# Sensor_Suite_1.net
KiCad netlist of a schematic drawn in Altium Designer
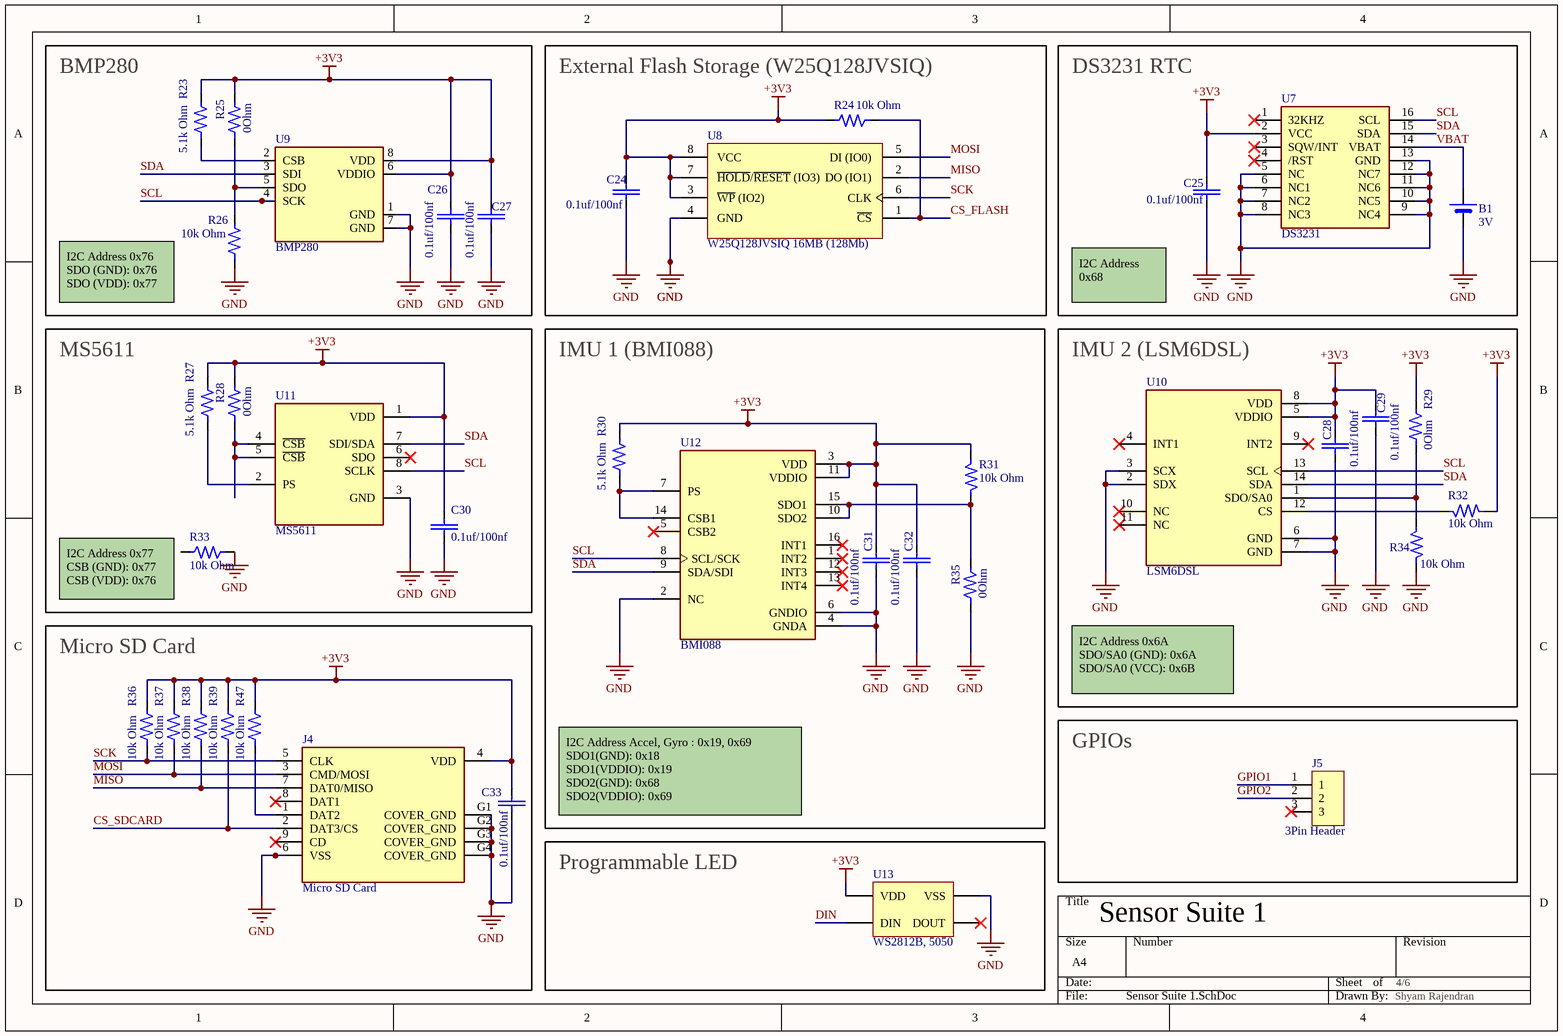
[diagram p0: Sensor Suite 1.SchDoc]

(export (version "E")
  (design (tool "Eeschema 10.0.6"))
  (components
    (comp (ref "B1")
      (value "3V")
      (footprint "Battery Holder")
      (description "CR2032 Button Cell")
      (libsource (lib "Sirius") (part "Button Cell"))
    )
    (comp (ref "C24")
      (value "0.1uf/100nf")
      (footprint "0.1uF Capacitor")
      (description "0.1 uF, Multilayer Ceramic Capacitor, 50 V, ï¿½ 10%, X7R, 0805 [2012 Metric]")
      (fields
        (field (name "MANUFACTURER") "Yageo")
        (field (name "MANUFACTURER PART NUMBER") "CC0805KRX7R9BB104")
      )
      (libsource (lib "Sirius") (part "CC0805KRX7R9BB104"))
    )
    (comp (ref "C25")
      (value "0.1uf/100nf")
      (footprint "0.1uF Capacitor")
      (description "0.1 uF, Multilayer Ceramic Capacitor, 50 V, ï¿½ 10%, X7R, 0805 [2012 Metric]")
      (fields
        (field (name "MANUFACTURER") "Yageo")
        (field (name "MANUFACTURER PART NUMBER") "CC0805KRX7R9BB104")
      )
      (libsource (lib "Sirius") (part "CC0805KRX7R9BB104"))
    )
    (comp (ref "C26")
      (value "0.1uf/100nf")
      (footprint "0.1uF Capacitor")
      (description "0.1 uF, Multilayer Ceramic Capacitor, 50 V, ï¿½ 10%, X7R, 0805 [2012 Metric]")
      (fields
        (field (name "MANUFACTURER") "Yageo")
        (field (name "MANUFACTURER PART NUMBER") "CC0805KRX7R9BB104")
      )
      (libsource (lib "Sirius") (part "CC0805KRX7R9BB104"))
    )
    (comp (ref "C27")
      (value "0.1uf/100nf")
      (footprint "0.1uF Capacitor")
      (description "0.1 uF, Multilayer Ceramic Capacitor, 50 V, ï¿½ 10%, X7R, 0805 [2012 Metric]")
      (fields
        (field (name "MANUFACTURER") "Yageo")
        (field (name "MANUFACTURER PART NUMBER") "CC0805KRX7R9BB104")
      )
      (libsource (lib "Sirius") (part "CC0805KRX7R9BB104"))
    )
    (comp (ref "C28")
      (value "0.1uf/100nf")
      (footprint "0.1uF Capacitor")
      (description "0.1 uF, Multilayer Ceramic Capacitor, 50 V, ï¿½ 10%, X7R, 0805 [2012 Metric]")
      (fields
        (field (name "MANUFACTURER") "Yageo")
        (field (name "MANUFACTURER PART NUMBER") "CC0805KRX7R9BB104")
      )
      (libsource (lib "Sirius") (part "CC0805KRX7R9BB104"))
    )
    (comp (ref "C29")
      (value "0.1uf/100nf")
      (footprint "0.1uF Capacitor")
      (description "0.1 uF, Multilayer Ceramic Capacitor, 50 V, ï¿½ 10%, X7R, 0805 [2012 Metric]")
      (fields
        (field (name "MANUFACTURER") "Yageo")
        (field (name "MANUFACTURER PART NUMBER") "CC0805KRX7R9BB104")
      )
      (libsource (lib "Sirius") (part "CC0805KRX7R9BB104"))
    )
    (comp (ref "C30")
      (value "0.1uf/100nf")
      (footprint "0.1uF Capacitor")
      (description "0.1 uF, Multilayer Ceramic Capacitor, 50 V, ï¿½ 10%, X7R, 0805 [2012 Metric]")
      (fields
        (field (name "MANUFACTURER") "Yageo")
        (field (name "MANUFACTURER PART NUMBER") "CC0805KRX7R9BB104")
      )
      (libsource (lib "Sirius") (part "CC0805KRX7R9BB104"))
    )
    (comp (ref "C31")
      (value "0.1uf/100nf")
      (footprint "0.1uF Capacitor")
      (description "0.1 uF, Multilayer Ceramic Capacitor, 50 V, ï¿½ 10%, X7R, 0805 [2012 Metric]")
      (fields
        (field (name "MANUFACTURER") "Yageo")
        (field (name "MANUFACTURER PART NUMBER") "CC0805KRX7R9BB104")
      )
      (libsource (lib "Sirius") (part "CC0805KRX7R9BB104"))
    )
    (comp (ref "C32")
      (value "0.1uf/100nf")
      (footprint "0.1uF Capacitor")
      (description "0.1 uF, Multilayer Ceramic Capacitor, 50 V, ï¿½ 10%, X7R, 0805 [2012 Metric]")
      (fields
        (field (name "MANUFACTURER") "Yageo")
        (field (name "MANUFACTURER PART NUMBER") "CC0805KRX7R9BB104")
      )
      (libsource (lib "Sirius") (part "CC0805KRX7R9BB104"))
    )
    (comp (ref "C33")
      (value "0.1uf/100nf")
      (footprint "0.1uF Capacitor")
      (description "0.1 uF, Multilayer Ceramic Capacitor, 50 V, ï¿½ 10%, X7R, 0805 [2012 Metric]")
      (fields
        (field (name "MANUFACTURER") "Yageo")
        (field (name "MANUFACTURER PART NUMBER") "CC0805KRX7R9BB104")
      )
      (libsource (lib "Sirius") (part "CC0805KRX7R9BB104"))
    )
    (comp (ref "J4")
      (value "Micro SD Card")
      (footprint "Micro SD Card")
      (fields (field (name "MF") "CUI Devices") (field (name "MP") "MSD-1-A"))
      (libsource (lib "Sirius") (part "Micro SD Card"))
    )
    (comp (ref "J5")
      (value "3Pin Header")
      (footprint "3 Pin Header")
      (libsource (lib "Sirius") (part "Header 3pin"))
    )
    (comp (ref "R23")
      (value "5.1k Ohm")
      (footprint "RESC2012X60N")
      (description "5.1k Ohm, 0805, 0.125W, 150V, 1% +/-Tol, 100ppm/Cel, Surface Mount")
      (fields
        (field (name "MANUFACTURER") "Yageo")
        (field (name "MANUFACTURER PART NUMBER") "RC0805FR-075K1L")
      )
      (libsource (lib "Sirius") (part "RC0805FR-075K1L"))
    )
    (comp (ref "R24")
      (value "10k Ohm")
      (footprint "RESC2013X60X35ML10T20")
      (description "10 kOhm, SMD Chip Resistor, ï¿½ 1%, 125 mW, 0805 [2012 Metric], Thick Film, General Purpose")
      (fields
        (field (name "MANUFACTURER") "Yageo")
        (field (name "MANUFACTURER PART NUMBER") "RC0805FR-0710KL")
      )
      (libsource (lib "Sirius") (part "RC0805FR-0710KL"))
    )
    (comp (ref "R25")
      (value "0Ohm")
      (footprint "1k 0805 Resistor")
      (description "0 Ohm Resistor, Jumper, 0805 [2012 Metric], Thick Film, 125 mW, Surface Mount")
      (fields
        (field (name "MANUFACTURER") "Vishay")
        (field (name "MANUFACTURER PART NUMBER") "CRCW08050000Z0EA")
      )
      (libsource (lib "Sirius") (part "CRCW08050000Z0EA"))
    )
    (comp (ref "R26")
      (value "10k Ohm")
      (footprint "RESC2013X60X35ML10T20")
      (description "10 kOhm, SMD Chip Resistor, ï¿½ 1%, 125 mW, 0805 [2012 Metric], Thick Film, General Purpose")
      (fields
        (field (name "MANUFACTURER") "Yageo")
        (field (name "MANUFACTURER PART NUMBER") "RC0805FR-0710KL")
      )
      (libsource (lib "Sirius") (part "RC0805FR-0710KL"))
    )
    (comp (ref "R27")
      (value "5.1k Ohm")
      (footprint "RESC2012X60N")
      (description "5.1k Ohm, 0805, 0.125W, 150V, 1% +/-Tol, 100ppm/Cel, Surface Mount")
      (fields
        (field (name "MANUFACTURER") "Yageo")
        (field (name "MANUFACTURER PART NUMBER") "RC0805FR-075K1L")
      )
      (libsource (lib "Sirius") (part "RC0805FR-075K1L"))
    )
    (comp (ref "R28")
      (value "0Ohm")
      (footprint "1k 0805 Resistor")
      (description "0 Ohm Resistor, Jumper, 0805 [2012 Metric], Thick Film, 125 mW, Surface Mount")
      (fields
        (field (name "MANUFACTURER") "Vishay")
        (field (name "MANUFACTURER PART NUMBER") "CRCW08050000Z0EA")
      )
      (libsource (lib "Sirius") (part "CRCW08050000Z0EA"))
    )
    (comp (ref "R29")
      (value "0Ohm")
      (footprint "1k 0805 Resistor")
      (description "0 Ohm Resistor, Jumper, 0805 [2012 Metric], Thick Film, 125 mW, Surface Mount")
      (fields
        (field (name "MANUFACTURER") "Vishay")
        (field (name "MANUFACTURER PART NUMBER") "CRCW08050000Z0EA")
      )
      (libsource (lib "Sirius") (part "CRCW08050000Z0EA"))
    )
    (comp (ref "R30")
      (value "5.1k Ohm")
      (footprint "RESC2012X60N")
      (description "5.1k Ohm, 0805, 0.125W, 150V, 1% +/-Tol, 100ppm/Cel, Surface Mount")
      (fields
        (field (name "MANUFACTURER") "Yageo")
        (field (name "MANUFACTURER PART NUMBER") "RC0805FR-075K1L")
      )
      (libsource (lib "Sirius") (part "RC0805FR-075K1L"))
    )
    (comp (ref "R31")
      (value "10k Ohm")
      (footprint "RESC2013X60X35ML10T20")
      (description "10 kOhm, SMD Chip Resistor, ï¿½ 1%, 125 mW, 0805 [2012 Metric], Thick Film, General Purpose")
      (fields
        (field (name "MANUFACTURER") "Yageo")
        (field (name "MANUFACTURER PART NUMBER") "RC0805FR-0710KL")
      )
      (libsource (lib "Sirius") (part "RC0805FR-0710KL"))
    )
    (comp (ref "R32")
      (value "10k Ohm")
      (footprint "RESC2013X60X35ML10T20")
      (description "10 kOhm, SMD Chip Resistor, ï¿½ 1%, 125 mW, 0805 [2012 Metric], Thick Film, General Purpose")
      (fields
        (field (name "MANUFACTURER") "Yageo")
        (field (name "MANUFACTURER PART NUMBER") "RC0805FR-0710KL")
      )
      (libsource (lib "Sirius") (part "RC0805FR-0710KL"))
    )
    (comp (ref "R33")
      (value "10k Ohm")
      (footprint "RESC2013X60X35ML10T20")
      (description "10 kOhm, SMD Chip Resistor, ï¿½ 1%, 125 mW, 0805 [2012 Metric], Thick Film, General Purpose")
      (fields
        (field (name "MANUFACTURER") "Yageo")
        (field (name "MANUFACTURER PART NUMBER") "RC0805FR-0710KL")
      )
      (libsource (lib "Sirius") (part "RC0805FR-0710KL"))
    )
    (comp (ref "R34")
      (value "10k Ohm")
      (footprint "RESC2013X60X35ML10T20")
      (description "10 kOhm, SMD Chip Resistor, ï¿½ 1%, 125 mW, 0805 [2012 Metric], Thick Film, General Purpose")
      (fields
        (field (name "MANUFACTURER") "Yageo")
        (field (name "MANUFACTURER PART NUMBER") "RC0805FR-0710KL")
      )
      (libsource (lib "Sirius") (part "RC0805FR-0710KL"))
    )
    (comp (ref "R35")
      (value "0Ohm")
      (footprint "1k 0805 Resistor")
      (description "0 Ohm Resistor, Jumper, 0805 [2012 Metric], Thick Film, 125 mW, Surface Mount")
      (fields
        (field (name "MANUFACTURER") "Vishay")
        (field (name "MANUFACTURER PART NUMBER") "CRCW08050000Z0EA")
      )
      (libsource (lib "Sirius") (part "CRCW08050000Z0EA"))
    )
    (comp (ref "R36")
      (value "10k Ohm")
      (footprint "RESC2013X60X35ML10T20")
      (description "10 kOhm, SMD Chip Resistor, ï¿½ 1%, 125 mW, 0805 [2012 Metric], Thick Film, General Purpose")
      (fields
        (field (name "MANUFACTURER") "Yageo")
        (field (name "MANUFACTURER PART NUMBER") "RC0805FR-0710KL")
      )
      (libsource (lib "Sirius") (part "RC0805FR-0710KL"))
    )
    (comp (ref "R37")
      (value "10k Ohm")
      (footprint "RESC2013X60X35ML10T20")
      (description "10 kOhm, SMD Chip Resistor, ï¿½ 1%, 125 mW, 0805 [2012 Metric], Thick Film, General Purpose")
      (fields
        (field (name "MANUFACTURER") "Yageo")
        (field (name "MANUFACTURER PART NUMBER") "RC0805FR-0710KL")
      )
      (libsource (lib "Sirius") (part "RC0805FR-0710KL"))
    )
    (comp (ref "R38")
      (value "10k Ohm")
      (footprint "RESC2013X60X35ML10T20")
      (description "10 kOhm, SMD Chip Resistor, ï¿½ 1%, 125 mW, 0805 [2012 Metric], Thick Film, General Purpose")
      (fields
        (field (name "MANUFACTURER") "Yageo")
        (field (name "MANUFACTURER PART NUMBER") "RC0805FR-0710KL")
      )
      (libsource (lib "Sirius") (part "RC0805FR-0710KL"))
    )
    (comp (ref "R39")
      (value "10k Ohm")
      (footprint "RESC2013X60X35ML10T20")
      (description "10 kOhm, SMD Chip Resistor, ï¿½ 1%, 125 mW, 0805 [2012 Metric], Thick Film, General Purpose")
      (fields
        (field (name "MANUFACTURER") "Yageo")
        (field (name "MANUFACTURER PART NUMBER") "RC0805FR-0710KL")
      )
      (libsource (lib "Sirius") (part "RC0805FR-0710KL"))
    )
    (comp (ref "R47")
      (value "10k Ohm")
      (footprint "RESC2013X60X35ML10T20")
      (description "10 kOhm, SMD Chip Resistor, ï¿½ 1%, 125 mW, 0805 [2012 Metric], Thick Film, General Purpose")
      (fields
        (field (name "MANUFACTURER") "Yageo")
        (field (name "MANUFACTURER PART NUMBER") "RC0805FR-0710KL")
      )
      (libsource (lib "Sirius") (part "RC0805FR-0710KL"))
    )
    (comp (ref "U7")
      (value "DS3231 RTC")
      (footprint "DS3231")
      (description "Real Time Clock (RTC) IC Clock/Calendar - IÂ²C, 2-Wire Serial 8-SOIC (0.154, 3.90mm Width)")
      (fields (field (name "MP") "DS3231") (field (name "MF") "Maxim Integrated"))
      (libsource (lib "Sirius") (part "DS3231"))
    )
    (comp (ref "U8")
      (value "W25Q128JVSIQ 16MB (128Mb)")
      (footprint "W25Q128JVSIQ")
      (description "16MB (128Mb) Flash, PDSO8")
      (fields
        (field (name "MANUFACTURER") "Winbond")
        (field (name "MANUFACTURER PART NUMBER") "W25Q128JVSIQ TR")
      )
      (libsource (lib "Sirius") (part "W25Q128JVSIQ TR"))
    )
    (comp (ref "U9")
      (value "BMP280")
      (footprint "BMP280")
      (description "BMP280 Absolute Barometric Pressure Sensor for Battery Powered Devices 2 x 2.5mm")
      (libsource (lib "Sirius") (part "BMP280"))
    )
    (comp (ref "U10")
      (value "LSM6DSL")
      (footprint "LSM6DSO32TR")
      (description "Accelerometer, Gyroscope, Temperature, 6 Axis Sensor IÂ²C, SPI Output")
      (fields (field (name "MF") "STMicroelectronics") (field (name "MP") "LSM6DSO32TR"))
      (libsource (lib "Sirius") (part "LSM6DSL"))
    )
    (comp (ref "U11")
      (value "MS5611")
      (footprint "MS561101BA03-50")
      (description "Sensor;MS5611-BT M-CAPS 3X5X1MM T&R;Pressure;MS561101BA03-50 ¦ TE Connectivity MS561101BA03-50")
      (fields (field (name "MF") "TE Connectivity") (field (name "MP") "MS561101BA03-50"))
      (libsource (lib "Sirius") (part "MS561101BA03-50"))
    )
    (comp (ref "U12") (value "BMI088") (footprint "BMI088") (libsource (lib "Sirius") (part "BMI088")))
    (comp (ref "U13")
      (value "WS2812B, 5050")
      (footprint "WS2812B")
      (fields (field (name "MANUFACTURER") "Adafruit-Industries-LLC"))
      (libsource (lib "Sirius") (part "WS2812B"))
    )
  )
  (nets
    (net (code "1") (name "+3V3") (class "Default")
      (node (ref "C24") (pin "1") (pinfunction "1_1") (pintype "passive"))
      (node (ref "C25") (pin "1") (pinfunction "1_1") (pintype "passive"))
      (node (ref "C26") (pin "2") (pinfunction "2_2") (pintype "passive"))
      (node (ref "C27") (pin "2") (pinfunction "2_2") (pintype "passive"))
      (node (ref "C28") (pin "2") (pinfunction "2_2") (pintype "passive"))
      (node (ref "C29") (pin "2") (pinfunction "2_2") (pintype "passive"))
      (node (ref "C30") (pin "2") (pinfunction "2_2") (pintype "passive"))
      (node (ref "C31") (pin "2") (pinfunction "2_2") (pintype "passive"))
      (node (ref "C32") (pin "2") (pinfunction "2_2") (pintype "passive"))
      (node (ref "C33") (pin "2") (pinfunction "2_2") (pintype "passive"))
      (node (ref "J4") (pin "4") (pinfunction "VDD_4") (pintype "passive"))
      (node (ref "R23") (pin "2") (pinfunction "2_2") (pintype "passive"))
      (node (ref "R24") (pin "2") (pinfunction "2_2") (pintype "passive"))
      (node (ref "R25") (pin "2") (pinfunction "2_2") (pintype "passive"))
      (node (ref "R27") (pin "2") (pinfunction "2_2") (pintype "passive"))
      (node (ref "R28") (pin "2") (pinfunction "2_2") (pintype "passive"))
      (node (ref "R29") (pin "2") (pinfunction "2_2") (pintype "passive"))
      (node (ref "R30") (pin "2") (pinfunction "2_2") (pintype "passive"))
      (node (ref "R31") (pin "2") (pinfunction "2_2") (pintype "passive"))
      (node (ref "R32") (pin "1") (pinfunction "1_1") (pintype "passive"))
      (node (ref "R36") (pin "2") (pinfunction "2_2") (pintype "passive"))
      (node (ref "R37") (pin "2") (pinfunction "2_2") (pintype "passive"))
      (node (ref "R38") (pin "2") (pinfunction "2_2") (pintype "passive"))
      (node (ref "R39") (pin "2") (pinfunction "2_2") (pintype "passive"))
      (node (ref "R47") (pin "2") (pinfunction "2_2") (pintype "passive"))
      (node (ref "U10") (pin "5") (pinfunction "VDDIO_5") (pintype "passive"))
      (node (ref "U10") (pin "8") (pinfunction "VDD_8") (pintype "passive"))
      (node (ref "U11") (pin "1") (pinfunction "VDD_1") (pintype "passive"))
      (node (ref "U12") (pin "11") (pinfunction "VDDIO_11") (pintype "passive"))
      (node (ref "U12") (pin "3") (pinfunction "VDD_3") (pintype "passive"))
      (node (ref "U13") (pin "VDD") (pinfunction "VDD_VDD") (pintype "passive"))
      (node (ref "U7") (pin "2") (pinfunction "VCC_2") (pintype "passive"))
      (node (ref "U8") (pin "3") (pinfunction "~{WP}_(IO2)_3") (pintype "passive"))
      (node (ref "U8") (pin "7") (pinfunction "~{HOLD}/~{RESET}_(IO3)_7") (pintype "passive"))
      (node (ref "U8") (pin "8") (pinfunction "VCC_8") (pintype "passive"))
      (node (ref "U9") (pin "6") (pinfunction "VDDIO_6") (pintype "passive"))
      (node (ref "U9") (pin "8") (pinfunction "VDD_8") (pintype "passive"))
    )
    (net (code "2") (name "/CS_FLASH") (class "Default")
      (node (ref "R24") (pin "1") (pinfunction "1_1") (pintype "passive"))
      (node (ref "U8") (pin "1") (pinfunction "~{CS}_1") (pintype "passive"))
    )
    (net (code "3") (name "/CS_SDCARD") (class "Default")
      (node (ref "J4") (pin "2") (pinfunction "DAT3/CS_2") (pintype "passive"))
      (node (ref "R39") (pin "1") (pinfunction "1_1") (pintype "passive"))
    )
    (net (code "4") (name "/DIN") (class "Default")
      (node (ref "U13") (pin "DIN") (pinfunction "DIN_DIN") (pintype "passive"))
    )
    (net (code "5") (name "/GPIO1") (class "Default")
      (node (ref "J5") (pin "1") (pinfunction "1_1") (pintype "passive"))
    )
    (net (code "6") (name "/GPIO2") (class "Default")
      (node (ref "J5") (pin "2") (pinfunction "2_2") (pintype "passive"))
    )
    (net (code "7") (name "/MISO") (class "Default")
      (node (ref "J4") (pin "7") (pinfunction "DAT0/MISO_7") (pintype "passive"))
      (node (ref "R38") (pin "1") (pinfunction "1_1") (pintype "passive"))
      (node (ref "U8") (pin "2") (pinfunction "DO_(IO1)_2") (pintype "passive"))
    )
    (net (code "8") (name "/MOSI") (class "Default")
      (node (ref "J4") (pin "3") (pinfunction "CMD/MOSI_3") (pintype "passive"))
      (node (ref "R37") (pin "1") (pinfunction "1_1") (pintype "passive"))
      (node (ref "U8") (pin "5") (pinfunction "DI_(IO0)_5") (pintype "passive"))
    )
    (net (code "9") (name "/SCK") (class "Default")
      (node (ref "J4") (pin "5") (pinfunction "CLK_5") (pintype "passive"))
      (node (ref "R36") (pin "1") (pinfunction "1_1") (pintype "passive"))
      (node (ref "U8") (pin "6") (pinfunction "CLK_6") (pintype "passive"))
    )
    (net (code "10") (name "/SCL") (class "Default")
      (node (ref "U10") (pin "13") (pinfunction "SCL_13") (pintype "passive"))
      (node (ref "U11") (pin "8") (pinfunction "SCLK_8") (pintype "passive"))
      (node (ref "U12") (pin "8") (pinfunction "SCL/SCK_8") (pintype "passive"))
      (node (ref "U7") (pin "16") (pinfunction "SCL_16") (pintype "passive"))
      (node (ref "U9") (pin "4") (pinfunction "SCK_4") (pintype "passive"))
    )
    (net (code "11") (name "/SDA") (class "Default")
      (node (ref "U10") (pin "14") (pinfunction "SDA_14") (pintype "passive"))
      (node (ref "U11") (pin "7") (pinfunction "SDI/SDA_7") (pintype "passive"))
      (node (ref "U12") (pin "9") (pinfunction "SDA/SDI_9") (pintype "passive"))
      (node (ref "U7") (pin "15") (pinfunction "SDA_15") (pintype "passive"))
      (node (ref "U9") (pin "3") (pinfunction "SDI_3") (pintype "passive"))
    )
    (net (code "12") (name "/VBAT") (class "Default")
      (node (ref "B1") (pin "P") (pinfunction "P_P") (pintype "passive"))
      (node (ref "U7") (pin "14") (pinfunction "VBAT_14") (pintype "passive"))
    )
    (net (code "13") (name "GND") (class "Default")
      (node (ref "B1") (pin "N") (pinfunction "N_N") (pintype "passive"))
      (node (ref "C24") (pin "2") (pinfunction "2_2") (pintype "passive"))
      (node (ref "C25") (pin "2") (pinfunction "2_2") (pintype "passive"))
      (node (ref "C26") (pin "1") (pinfunction "1_1") (pintype "passive"))
      (node (ref "C27") (pin "1") (pinfunction "1_1") (pintype "passive"))
      (node (ref "C28") (pin "1") (pinfunction "1_1") (pintype "passive"))
      (node (ref "C29") (pin "1") (pinfunction "1_1") (pintype "passive"))
      (node (ref "C30") (pin "1") (pinfunction "1_1") (pintype "passive"))
      (node (ref "C31") (pin "1") (pinfunction "1_1") (pintype "passive"))
      (node (ref "C32") (pin "1") (pinfunction "1_1") (pintype "passive"))
      (node (ref "C33") (pin "1") (pinfunction "1_1") (pintype "passive"))
      (node (ref "J4") (pin "6") (pinfunction "VSS_6") (pintype "passive"))
      (node (ref "J4") (pin "G1") (pinfunction "COVER_GND_G1") (pintype "passive"))
      (node (ref "J4") (pin "G2") (pinfunction "COVER_GND_G2") (pintype "passive"))
      (node (ref "J4") (pin "G3") (pinfunction "COVER_GND_G3") (pintype "passive"))
      (node (ref "J4") (pin "G4") (pinfunction "COVER_GND_G4") (pintype "passive"))
      (node (ref "R26") (pin "1") (pinfunction "1_1") (pintype "passive"))
      (node (ref "R33") (pin "1") (pinfunction "1_1") (pintype "passive"))
      (node (ref "R34") (pin "1") (pinfunction "1_1") (pintype "passive"))
      (node (ref "R35") (pin "1") (pinfunction "1_1") (pintype "passive"))
      (node (ref "U10") (pin "2") (pinfunction "SDX_2") (pintype "passive"))
      (node (ref "U10") (pin "3") (pinfunction "SCX_3") (pintype "passive"))
      (node (ref "U10") (pin "6") (pinfunction "GND_6") (pintype "passive"))
      (node (ref "U10") (pin "7") (pinfunction "GND_7") (pintype "passive"))
      (node (ref "U11") (pin "3") (pinfunction "GND_3") (pintype "passive"))
      (node (ref "U12") (pin "2") (pinfunction "NC_2") (pintype "passive"))
      (node (ref "U12") (pin "4") (pinfunction "GNDA_4") (pintype "passive"))
      (node (ref "U12") (pin "6") (pinfunction "GNDIO_6") (pintype "passive"))
      (node (ref "U13") (pin "VSS") (pinfunction "VSS_VSS") (pintype "passive"))
      (node (ref "U7") (pin "10") (pinfunction "NC5_10") (pintype "passive"))
      (node (ref "U7") (pin "11") (pinfunction "NC6_11") (pintype "passive"))
      (node (ref "U7") (pin "12") (pinfunction "NC7_12") (pintype "passive"))
      (node (ref "U7") (pin "13") (pinfunction "GND_13") (pintype "passive"))
      (node (ref "U7") (pin "5") (pinfunction "NC_5") (pintype "passive"))
      (node (ref "U7") (pin "6") (pinfunction "NC1_6") (pintype "passive"))
      (node (ref "U7") (pin "7") (pinfunction "NC2_7") (pintype "passive"))
      (node (ref "U7") (pin "8") (pinfunction "NC3_8") (pintype "passive"))
      (node (ref "U7") (pin "9") (pinfunction "NC4_9") (pintype "passive"))
      (node (ref "U8") (pin "4") (pinfunction "GND_4") (pintype "passive"))
      (node (ref "U9") (pin "1") (pinfunction "GND_1") (pintype "passive"))
      (node (ref "U9") (pin "7") (pinfunction "GND_7") (pintype "passive"))
    )
    (net (code "14") (name "Net-(J4-DAT2)") (class "Default")
      (node (ref "J4") (pin "1") (pinfunction "DAT2_1") (pintype "passive"))
      (node (ref "R47") (pin "1") (pinfunction "1_1") (pintype "passive"))
    )
    (net (code "15") (name "Net-(R28-Pad1)") (class "Default")
      (node (ref "R28") (pin "1") (pinfunction "1_1") (pintype "passive"))
      (node (ref "U11") (pin "4") (pinfunction "~{CSB}_4") (pintype "passive"))
      (node (ref "U11") (pin "5") (pinfunction "~{CSB}_5") (pintype "passive"))
    )
    (net (code "16") (name "Net-(U9-CSB)") (class "Default")
      (node (ref "R23") (pin "1") (pinfunction "1_1") (pintype "passive"))
      (node (ref "U9") (pin "2") (pinfunction "CSB_2") (pintype "passive"))
    )
    (net (code "17") (name "Net-(U9-SDO)") (class "Default")
      (node (ref "R25") (pin "1") (pinfunction "1_1") (pintype "passive"))
      (node (ref "R26") (pin "2") (pinfunction "2_2") (pintype "passive"))
      (node (ref "U9") (pin "5") (pinfunction "SDO_5") (pintype "passive"))
    )
    (net (code "18") (name "Net-(U10-CS)") (class "Default")
      (node (ref "R32") (pin "2") (pinfunction "2_2") (pintype "passive"))
      (node (ref "U10") (pin "12") (pinfunction "CS_12") (pintype "passive"))
    )
    (net (code "19") (name "Net-(U10-SDO{slash}SA0)") (class "Default")
      (node (ref "R29") (pin "1") (pinfunction "1_1") (pintype "passive"))
      (node (ref "R34") (pin "2") (pinfunction "2_2") (pintype "passive"))
      (node (ref "U10") (pin "1") (pinfunction "SDO/SA0_1") (pintype "passive"))
    )
    (net (code "20") (name "Net-(U11-PS)") (class "Default")
      (node (ref "R27") (pin "1") (pinfunction "1_1") (pintype "passive"))
      (node (ref "U11") (pin "2") (pinfunction "PS_2") (pintype "passive"))
    )
    (net (code "21") (name "Net-(U12-CSB1)") (class "Default")
      (node (ref "R30") (pin "1") (pinfunction "1_1") (pintype "passive"))
      (node (ref "U12") (pin "14") (pinfunction "CSB1_14") (pintype "passive"))
      (node (ref "U12") (pin "7") (pinfunction "PS_7") (pintype "passive"))
    )
    (net (code "22") (name "Net-(U12-SDO1)") (class "Default")
      (node (ref "R31") (pin "1") (pinfunction "1_1") (pintype "passive"))
      (node (ref "R35") (pin "2") (pinfunction "2_2") (pintype "passive"))
      (node (ref "U12") (pin "10") (pinfunction "SDO2_10") (pintype "passive"))
      (node (ref "U12") (pin "15") (pinfunction "SDO1_15") (pintype "passive"))
    )
    (net (code "23") (name "unconnected-(J4-CD-Pad9)") (class "Default")
      (node (ref "J4") (pin "9") (pinfunction "CD_9") (pintype "passive+no_connect"))
    )
    (net (code "24") (name "unconnected-(J4-DAT1-Pad8)") (class "Default")
      (node (ref "J4") (pin "8") (pinfunction "DAT1_8") (pintype "passive+no_connect"))
    )
    (net (code "25") (name "unconnected-(J5-Pad3)") (class "Default")
      (node (ref "J5") (pin "3") (pinfunction "3_3") (pintype "passive+no_connect"))
    )
    (net (code "26") (name "unconnected-(R33-Pad2)") (class "Default")
      (node (ref "R33") (pin "2") (pinfunction "2_2") (pintype "passive"))
    )
    (net (code "27") (name "unconnected-(U7-32KHZ-Pad1)") (class "Default")
      (node (ref "U7") (pin "1") (pinfunction "32KHZ_1") (pintype "passive+no_connect"))
    )
    (net (code "28") (name "unconnected-(U7-SQW{slash}INT-Pad3)") (class "Default")
      (node (ref "U7") (pin "3") (pinfunction "SQW/INT_3") (pintype "passive+no_connect"))
    )
    (net (code "29") (name "unconnected-(U7-{slash}RST-Pad4)") (class "Default")
      (node (ref "U7") (pin "4") (pinfunction "/RST_4") (pintype "passive+no_connect"))
    )
    (net (code "30") (name "unconnected-(U10-INT1-Pad4)") (class "Default")
      (node (ref "U10") (pin "4") (pinfunction "INT1_4") (pintype "passive+no_connect"))
    )
    (net (code "31") (name "unconnected-(U10-INT2-Pad9)") (class "Default")
      (node (ref "U10") (pin "9") (pinfunction "INT2_9") (pintype "passive+no_connect"))
    )
    (net (code "32") (name "unconnected-(U10-NC-Pad10)") (class "Default")
      (node (ref "U10") (pin "10") (pinfunction "NC_10") (pintype "passive+no_connect"))
    )
    (net (code "33") (name "unconnected-(U10-NC-Pad11)") (class "Default")
      (node (ref "U10") (pin "11") (pinfunction "NC_11") (pintype "passive+no_connect"))
    )
    (net (code "34") (name "unconnected-(U11-SDO-Pad6)") (class "Default")
      (node (ref "U11") (pin "6") (pinfunction "SDO_6") (pintype "passive+no_connect"))
    )
    (net (code "35") (name "unconnected-(U12-CSB2-Pad5)") (class "Default")
      (node (ref "U12") (pin "5") (pinfunction "CSB2_5") (pintype "passive+no_connect"))
    )
    (net (code "36") (name "unconnected-(U12-INT1-Pad16)") (class "Default")
      (node (ref "U12") (pin "16") (pinfunction "INT1_16") (pintype "passive+no_connect"))
    )
    (net (code "37") (name "unconnected-(U12-INT2-Pad1)") (class "Default")
      (node (ref "U12") (pin "1") (pinfunction "INT2_1") (pintype "passive+no_connect"))
    )
    (net (code "38") (name "unconnected-(U12-INT3-Pad12)") (class "Default")
      (node (ref "U12") (pin "12") (pinfunction "INT3_12") (pintype "passive+no_connect"))
    )
    (net (code "39") (name "unconnected-(U12-INT4-Pad13)") (class "Default")
      (node (ref "U12") (pin "13") (pinfunction "INT4_13") (pintype "passive+no_connect"))
    )
    (net (code "40") (name "unconnected-(U13-PadDOUT)") (class "Default")
      (node (ref "U13") (pin "DOUT") (pinfunction "DOUT_DOUT") (pintype "passive+no_connect"))
    )
  )
)
